# FC.net
KiCad netlist of a schematic drawn in Altium Designer
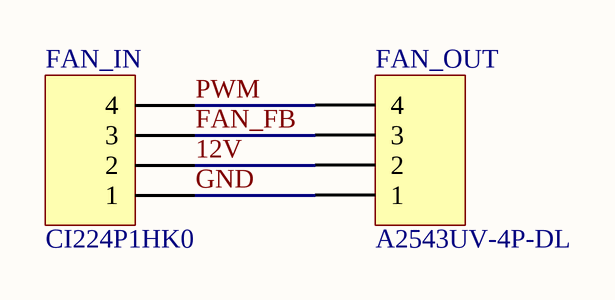
[diagram p0: FC.SchDoc]

(export (version "E")
  (design (tool "Eeschema 10.0.6"))
  (components
    (comp (ref "FAN_IN")
      (value "CI224P1HK0")
      (footprint "XH-4AW")
      (description "Header, 4-Pin, Right Angle")
      (fields (field (name "PUBLISHER") "Altium Limited"))
      (libsource (lib "") (part "Header 4H_1"))
    )
    (comp (ref "FAN_OUT")
      (value "A2543UV-4P-DL")
      (footprint "FAN")
      (description "Header, 4-Pin, Right Angle")
      (fields (field (name "PUBLISHER") "Altium Limited"))
      (libsource (lib "Miscellaneous Connectors") (part "Header 4H"))
    )
  )
  (nets
    (net (code "1") (name "/12V") (class "Default")
      (node (ref "FAN_IN") (pin "2") (pinfunction "2_2") (pintype "passive"))
      (node (ref "FAN_OUT") (pin "2") (pinfunction "2_2") (pintype "passive"))
    )
    (net (code "2") (name "/FAN_FB") (class "Default")
      (node (ref "FAN_IN") (pin "3") (pinfunction "3_3") (pintype "passive"))
      (node (ref "FAN_OUT") (pin "3") (pinfunction "3_3") (pintype "passive"))
    )
    (net (code "3") (name "/GND") (class "Default")
      (node (ref "FAN_IN") (pin "1") (pinfunction "1_1") (pintype "passive"))
      (node (ref "FAN_OUT") (pin "1") (pinfunction "1_1") (pintype "passive"))
    )
    (net (code "4") (name "/PWM") (class "Default")
      (node (ref "FAN_IN") (pin "4") (pinfunction "4_4") (pintype "passive"))
      (node (ref "FAN_OUT") (pin "4") (pinfunction "4_4") (pintype "passive"))
    )
  )
)
